# InputSwitch.net
KiCad netlist of a schematic drawn in EAGLE
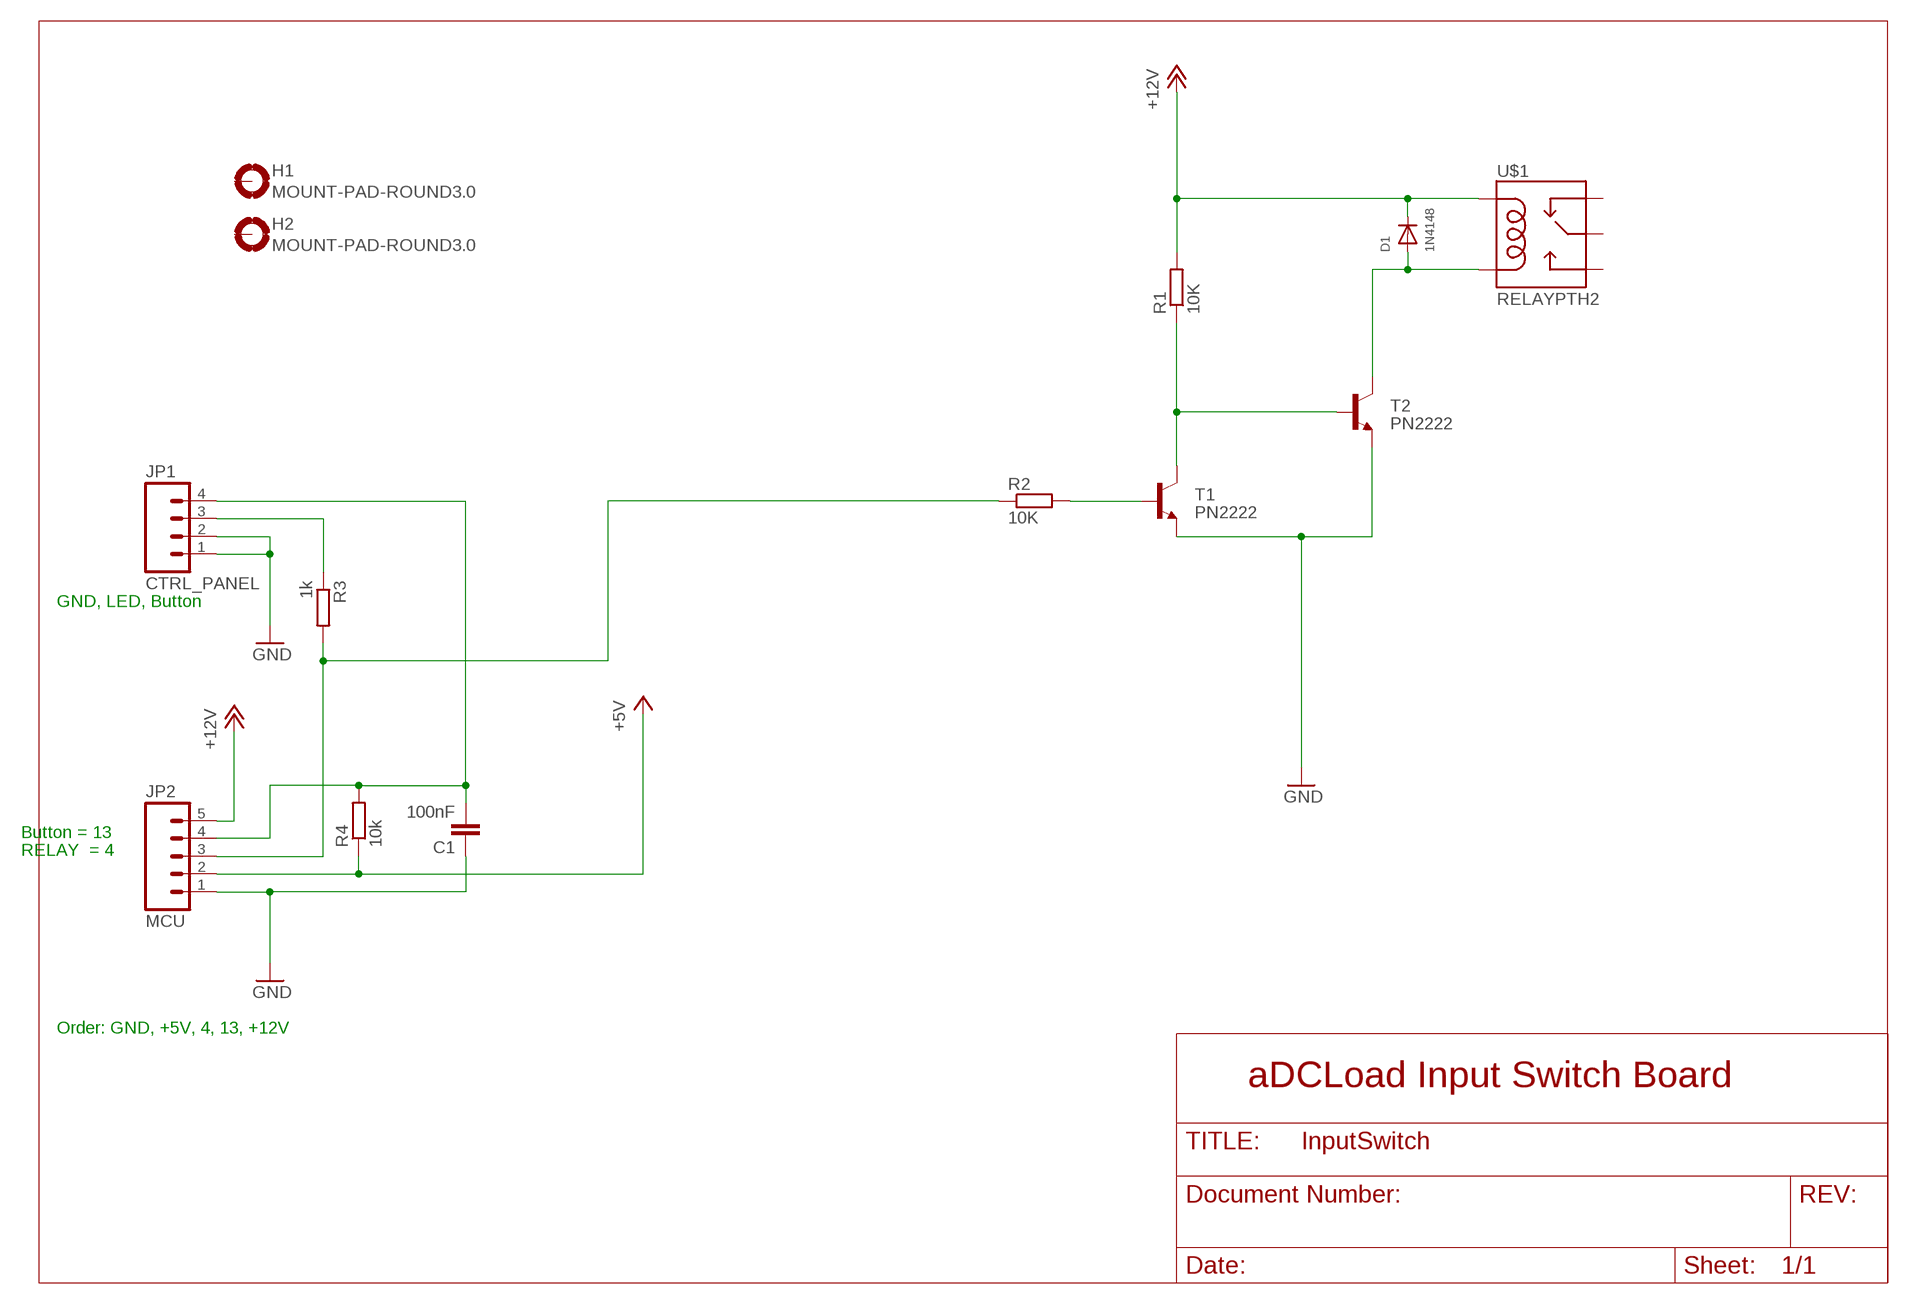
[diagram p0: schematic, sheet 1]

(export (version "E")
  (design (tool "Eeschema 10.0.6"))
  (components
    (comp (ref "C1")
      (value "100nF")
      (footprint "eagle-import:C0805")
      (libsource (lib "eagle-import") (part "C-EUC0805"))
    )
    (comp (ref "D1")
      (value "1N4148")
      (footprint "eagle-import:SOD-123")
      (libsource (lib "eagle-import") (part "DIODESOD-123"))
    )
    (comp (ref "H1")
      (value "MOUNT-PAD-ROUND3.0")
      (footprint "eagle-import:3,0-PAD")
      (libsource (lib "eagle-import") (part "MOUNT-PAD-ROUND3.0"))
    )
    (comp (ref "H2")
      (value "MOUNT-PAD-ROUND3.0")
      (footprint "eagle-import:3,0-PAD")
      (libsource (lib "eagle-import") (part "MOUNT-PAD-ROUND3.0"))
    )
    (comp (ref "JP1")
      (value "CTRL_PANEL")
      (footprint "eagle-import:1X04")
      (libsource (lib "eagle-import") (part "M04PTH"))
    )
    (comp (ref "JP2")
      (value "MCU")
      (footprint "eagle-import:1X05")
      (libsource (lib "eagle-import") (part "M05PTH"))
    )
    (comp (ref "R1")
      (value "10K")
      (footprint "eagle-import:R0805")
      (libsource (lib "eagle-import") (part "R-EU_R0805"))
    )
    (comp (ref "R2")
      (value "10K")
      (footprint "eagle-import:R0805")
      (libsource (lib "eagle-import") (part "R-EU_R0805"))
    )
    (comp (ref "R3")
      (value "1k")
      (footprint "eagle-import:R0805")
      (libsource (lib "eagle-import") (part "R-EU_R0805"))
    )
    (comp (ref "R4")
      (value "10k")
      (footprint "eagle-import:R0805")
      (libsource (lib "eagle-import") (part "R-EU_R0805"))
    )
    (comp (ref "T1")
      (value "PN2222")
      (footprint "eagle-import:SOT23-3")
      (libsource (lib "eagle-import") (part "TRANSISTOR_NPNMMBT2222A"))
    )
    (comp (ref "T2")
      (value "PN2222")
      (footprint "eagle-import:SOT23-3")
      (libsource (lib "eagle-import") (part "TRANSISTOR_NPNMMBT2222A"))
    )
    (comp (ref "U$1")
      (value "RELAYPTH2")
      (footprint "eagle-import:RELAY-T9A")
      (libsource (lib "eagle-import") (part "RELAYPTH2"))
    )
  )
  (nets
    (net (code "1") (name "+5V") (class "Default")
      (node (ref "JP2") (pin "2") (pinfunction "2_2") (pintype "passive"))
      (node (ref "R4") (pin "1") (pinfunction "1_1") (pintype "passive"))
    )
    (net (code "2") (name "+12V") (class "Default")
      (node (ref "D1") (pin "C") (pinfunction "C_C") (pintype "passive"))
      (node (ref "JP2") (pin "5") (pinfunction "5_5") (pintype "passive"))
      (node (ref "R1") (pin "2") (pinfunction "2_2") (pintype "passive"))
      (node (ref "U$1") (pin "COIL1") (pinfunction "COIL1_COIL1") (pintype "bidirectional"))
    )
    (net (code "3") (name "GND") (class "Default")
      (node (ref "C1") (pin "1") (pinfunction "1_1") (pintype "passive"))
      (node (ref "JP1") (pin "1") (pinfunction "1_1") (pintype "passive"))
      (node (ref "JP1") (pin "2") (pinfunction "2_2") (pintype "passive"))
      (node (ref "JP2") (pin "1") (pinfunction "1_1") (pintype "passive"))
      (node (ref "T1") (pin "2") (pinfunction "E_2") (pintype "passive"))
      (node (ref "T2") (pin "2") (pinfunction "E_2") (pintype "passive"))
    )
    (net (code "4") (name "Net-(C1-Pad2)") (class "Default")
      (node (ref "C1") (pin "2") (pinfunction "2_2") (pintype "passive"))
      (node (ref "JP1") (pin "4") (pinfunction "4_4") (pintype "passive"))
      (node (ref "JP2") (pin "4") (pinfunction "4_4") (pintype "passive"))
      (node (ref "R4") (pin "2") (pinfunction "2_2") (pintype "passive"))
    )
    (net (code "5") (name "Net-(JP1-Pad3)") (class "Default")
      (node (ref "JP1") (pin "3") (pinfunction "3_3") (pintype "passive"))
      (node (ref "R3") (pin "1") (pinfunction "1_1") (pintype "passive"))
    )
    (net (code "6") (name "Net-(JP2-Pad3)") (class "Default")
      (node (ref "JP2") (pin "3") (pinfunction "3_3") (pintype "passive"))
      (node (ref "R2") (pin "1") (pinfunction "1_1") (pintype "passive"))
      (node (ref "R3") (pin "2") (pinfunction "2_2") (pintype "passive"))
    )
    (net (code "7") (name "Net-(T1-B)") (class "Default")
      (node (ref "R2") (pin "2") (pinfunction "2_2") (pintype "passive"))
      (node (ref "T1") (pin "1") (pinfunction "B_1") (pintype "passive"))
    )
    (net (code "8") (name "Net-(T1-C)") (class "Default")
      (node (ref "R1") (pin "1") (pinfunction "1_1") (pintype "passive"))
      (node (ref "T1") (pin "3") (pinfunction "C_3") (pintype "passive"))
      (node (ref "T2") (pin "1") (pinfunction "B_1") (pintype "passive"))
    )
    (net (code "9") (name "Net-(T2-C)") (class "Default")
      (node (ref "D1") (pin "A") (pinfunction "A_A") (pintype "passive"))
      (node (ref "T2") (pin "3") (pinfunction "C_3") (pintype "passive"))
      (node (ref "U$1") (pin "COIL2") (pinfunction "COIL2_COIL2") (pintype "bidirectional"))
    )
    (net (code "10") (name "unconnected-(H1-MOUNT-PadB3,0)") (class "Default")
      (node (ref "H1") (pin "B3,0") (pinfunction "MOUNT_B3,0") (pintype "passive"))
    )
    (net (code "11") (name "unconnected-(H2-MOUNT-PadB3,0)") (class "Default")
      (node (ref "H2") (pin "B3,0") (pinfunction "MOUNT_B3,0") (pintype "passive"))
    )
    (net (code "12") (name "unconnected-(U$1-PadMAIN)") (class "Default")
      (node (ref "U$1") (pin "MAIN") (pinfunction "MAIN_MAIN") (pintype "bidirectional"))
    )
    (net (code "13") (name "unconnected-(U$1-PadNC)") (class "Default")
      (node (ref "U$1") (pin "NC") (pinfunction "NC_NC") (pintype "bidirectional"))
    )
    (net (code "14") (name "unconnected-(U$1-PadNO)") (class "Default")
      (node (ref "U$1") (pin "NO") (pinfunction "NO_NO") (pintype "bidirectional"))
    )
  )
)
